# fabduck_01.net
KiCad netlist of a schematic drawn in EAGLE
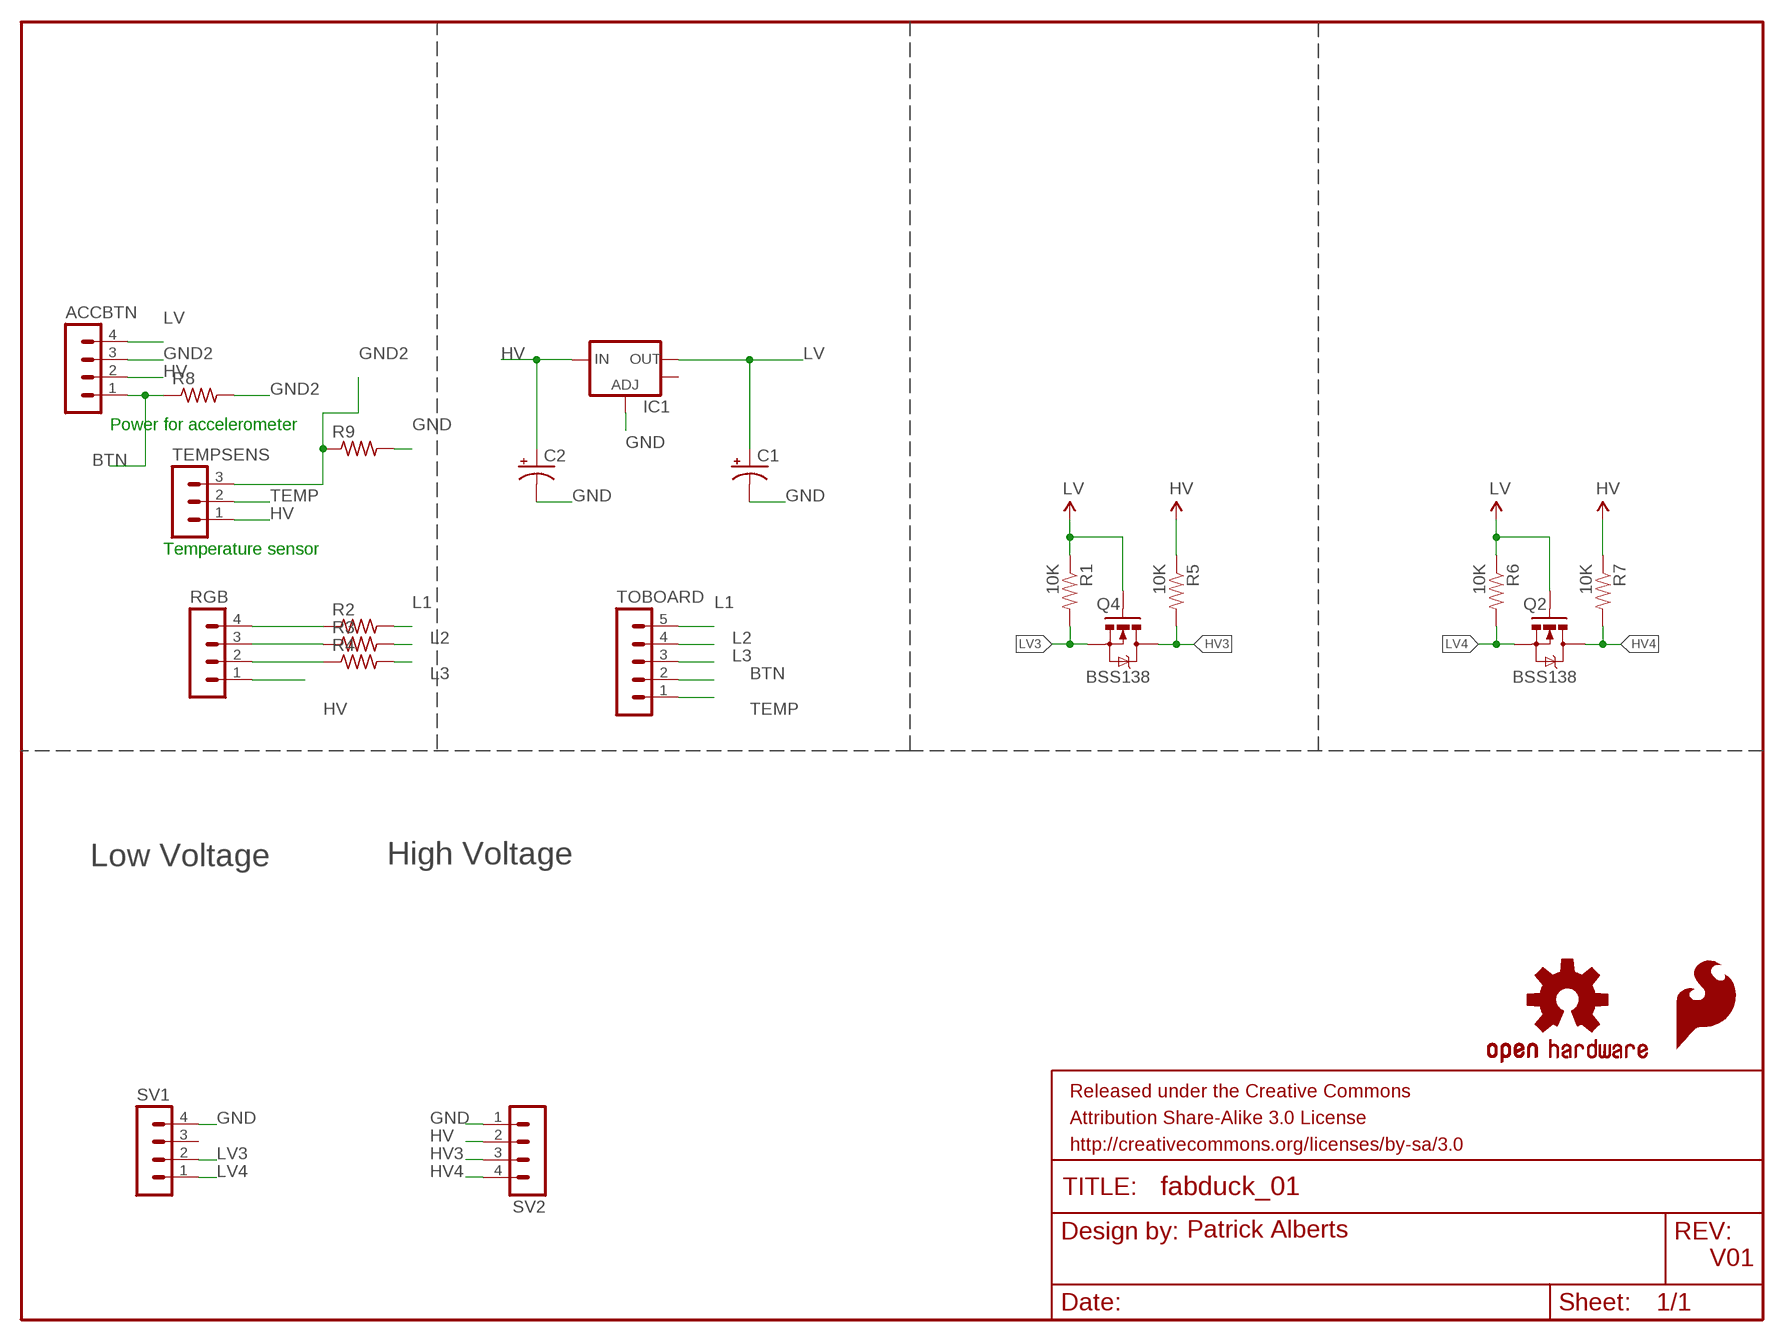
[diagram p0: schematic, sheet 1]

(export (version "E")
  (design (tool "Eeschema 10.0.6"))
  (components
    (comp (ref "ACCBTN")
      (value "MA04-1")
      (footprint "eagle-import:MA04-1")
      (libsource (lib "eagle-import") (part "MA04-1"))
    )
    (comp (ref "C1")
      (value "CAP_POLD")
      (footprint "eagle-import:PANASONIC_D")
      (libsource (lib "eagle-import") (part "CAP_POLD"))
    )
    (comp (ref "C2")
      (value "CAP_POLD")
      (footprint "eagle-import:PANASONIC_D")
      (libsource (lib "eagle-import") (part "CAP_POLD"))
    )
    (comp (ref "IC1")
      (value "V_REG_LM1117SOT223")
      (footprint "eagle-import:SOT223")
      (libsource (lib "eagle-import") (part "V_REG_LM1117SOT223"))
    )
    (comp (ref "LOGO1")
      (value "SFE_LOGO_FLAME.1_INCH")
      (footprint "eagle-import:SFE_LOGO_FLAME_.1")
      (libsource (lib "eagle-import") (part "SFE_LOGO_FLAME.1_INCH"))
    )
    (comp (ref "LOGO2")
      (value "OSHW-LOGOS")
      (footprint "eagle-import:OSHW-LOGO-S")
      (libsource (lib "eagle-import") (part "OSHW-LOGOS"))
    )
    (comp (ref "Q2")
      (value "BSS138")
      (footprint "eagle-import:SOT23-3")
      (libsource (lib "eagle-import") (part "MOSFET-NCHANNELSMD"))
    )
    (comp (ref "Q4")
      (value "BSS138")
      (footprint "eagle-import:SOT23-3")
      (libsource (lib "eagle-import") (part "MOSFET-NCHANNELSMD"))
    )
    (comp (ref "R1")
      (value "10K")
      (footprint "eagle-import:0603-RES")
      (libsource (lib "eagle-import") (part "RESISTOR0603-RES"))
    )
    (comp (ref "R2")
      (value "RESISTOR1206")
      (footprint "eagle-import:1206")
      (libsource (lib "eagle-import") (part "RESISTOR1206"))
    )
    (comp (ref "R3")
      (value "RESISTOR1206")
      (footprint "eagle-import:1206")
      (libsource (lib "eagle-import") (part "RESISTOR1206"))
    )
    (comp (ref "R4")
      (value "RESISTOR1206")
      (footprint "eagle-import:1206")
      (libsource (lib "eagle-import") (part "RESISTOR1206"))
    )
    (comp (ref "R5")
      (value "10K")
      (footprint "eagle-import:0603-RES")
      (libsource (lib "eagle-import") (part "RESISTOR0603-RES"))
    )
    (comp (ref "R6")
      (value "10K")
      (footprint "eagle-import:0603-RES")
      (libsource (lib "eagle-import") (part "RESISTOR0603-RES"))
    )
    (comp (ref "R7")
      (value "10K")
      (footprint "eagle-import:0603-RES")
      (libsource (lib "eagle-import") (part "RESISTOR0603-RES"))
    )
    (comp (ref "R8")
      (value "RESISTOR1206")
      (footprint "eagle-import:1206")
      (libsource (lib "eagle-import") (part "RESISTOR1206"))
    )
    (comp (ref "R9")
      (value "RESISTOR1206")
      (footprint "eagle-import:1206")
      (libsource (lib "eagle-import") (part "RESISTOR1206"))
    )
    (comp (ref "RGB")
      (value "MA04-1")
      (footprint "eagle-import:MA04-1")
      (libsource (lib "eagle-import") (part "MA04-1"))
    )
    (comp (ref "SV1")
      (value "MA04-1")
      (footprint "eagle-import:MA04-1")
      (libsource (lib "eagle-import") (part "MA04-1"))
    )
    (comp (ref "SV2")
      (value "MA04-1")
      (footprint "eagle-import:MA04-1")
      (libsource (lib "eagle-import") (part "MA04-1"))
    )
    (comp (ref "TEMPSENS")
      (value "MA03-1")
      (footprint "eagle-import:MA03-1")
      (libsource (lib "eagle-import") (part "MA03-1"))
    )
    (comp (ref "TOBOARD")
      (value "MA05-1")
      (footprint "eagle-import:MA05-1")
      (libsource (lib "eagle-import") (part "MA05-1"))
    )
  )
  (nets
    (net (code "1") (name "/BTN") (class "Default")
      (node (ref "ACCBTN") (pin "1") (pinfunction "1_1") (pintype "passive"))
      (node (ref "R8") (pin "1") (pinfunction "1_1") (pintype "passive"))
      (node (ref "TOBOARD") (pin "2") (pinfunction "2_2") (pintype "passive"))
    )
    (net (code "2") (name "/GND") (class "Default")
      (node (ref "C1") (pin "-") (pinfunction "-_-") (pintype "passive"))
      (node (ref "C2") (pin "-") (pinfunction "-_-") (pintype "passive"))
      (node (ref "IC1") (pin "1") (pinfunction "ADJ_1") (pintype "input"))
      (node (ref "R9") (pin "2") (pinfunction "2_2") (pintype "passive"))
      (node (ref "SV1") (pin "4") (pinfunction "4_4") (pintype "passive"))
      (node (ref "SV2") (pin "1") (pinfunction "1_1") (pintype "passive"))
    )
    (net (code "3") (name "/GND2") (class "Default")
      (node (ref "ACCBTN") (pin "3") (pinfunction "3_3") (pintype "passive"))
      (node (ref "R8") (pin "2") (pinfunction "2_2") (pintype "passive"))
      (node (ref "R9") (pin "1") (pinfunction "1_1") (pintype "passive"))
      (node (ref "TEMPSENS") (pin "3") (pinfunction "3_3") (pintype "passive"))
    )
    (net (code "4") (name "/L1") (class "Default")
      (node (ref "R2") (pin "2") (pinfunction "2_2") (pintype "passive"))
      (node (ref "TOBOARD") (pin "5") (pinfunction "5_5") (pintype "passive"))
    )
    (net (code "5") (name "/L2") (class "Default")
      (node (ref "R3") (pin "2") (pinfunction "2_2") (pintype "passive"))
      (node (ref "TOBOARD") (pin "4") (pinfunction "4_4") (pintype "passive"))
    )
    (net (code "6") (name "/L3") (class "Default")
      (node (ref "R4") (pin "2") (pinfunction "2_2") (pintype "passive"))
      (node (ref "TOBOARD") (pin "3") (pinfunction "3_3") (pintype "passive"))
    )
    (net (code "7") (name "/TEMP") (class "Default")
      (node (ref "TEMPSENS") (pin "2") (pinfunction "2_2") (pintype "passive"))
      (node (ref "TOBOARD") (pin "1") (pinfunction "1_1") (pintype "passive"))
    )
    (net (code "8") (name "HV") (class "Default")
      (node (ref "ACCBTN") (pin "2") (pinfunction "2_2") (pintype "passive"))
      (node (ref "C2") (pin "+") (pinfunction "+_+") (pintype "passive"))
      (node (ref "IC1") (pin "3") (pinfunction "IN_3") (pintype "input"))
      (node (ref "R5") (pin "1") (pinfunction "1_1") (pintype "passive"))
      (node (ref "R7") (pin "1") (pinfunction "1_1") (pintype "passive"))
      (node (ref "RGB") (pin "1") (pinfunction "1_1") (pintype "passive"))
      (node (ref "SV2") (pin "2") (pinfunction "2_2") (pintype "passive"))
      (node (ref "TEMPSENS") (pin "1") (pinfunction "1_1") (pintype "passive"))
    )
    (net (code "9") (name "HV3") (class "Default")
      (node (ref "Q4") (pin "3") (pinfunction "D_3") (pintype "passive"))
      (node (ref "R5") (pin "2") (pinfunction "2_2") (pintype "passive"))
      (node (ref "SV2") (pin "3") (pinfunction "3_3") (pintype "passive"))
    )
    (net (code "10") (name "HV4") (class "Default")
      (node (ref "Q2") (pin "3") (pinfunction "D_3") (pintype "passive"))
      (node (ref "R7") (pin "2") (pinfunction "2_2") (pintype "passive"))
      (node (ref "SV2") (pin "4") (pinfunction "4_4") (pintype "passive"))
    )
    (net (code "11") (name "LV") (class "Default")
      (node (ref "ACCBTN") (pin "4") (pinfunction "4_4") (pintype "passive"))
      (node (ref "C1") (pin "+") (pinfunction "+_+") (pintype "passive"))
      (node (ref "IC1") (pin "2") (pinfunction "OUT_2") (pintype "output"))
      (node (ref "Q2") (pin "1") (pinfunction "G_1") (pintype "passive"))
      (node (ref "Q4") (pin "1") (pinfunction "G_1") (pintype "passive"))
      (node (ref "R1") (pin "1") (pinfunction "1_1") (pintype "passive"))
      (node (ref "R6") (pin "1") (pinfunction "1_1") (pintype "passive"))
    )
    (net (code "12") (name "LV3") (class "Default")
      (node (ref "Q4") (pin "2") (pinfunction "S_2") (pintype "passive"))
      (node (ref "R1") (pin "2") (pinfunction "2_2") (pintype "passive"))
      (node (ref "SV1") (pin "2") (pinfunction "2_2") (pintype "passive"))
    )
    (net (code "13") (name "LV4") (class "Default")
      (node (ref "Q2") (pin "2") (pinfunction "S_2") (pintype "passive"))
      (node (ref "R6") (pin "2") (pinfunction "2_2") (pintype "passive"))
      (node (ref "SV1") (pin "1") (pinfunction "1_1") (pintype "passive"))
    )
    (net (code "14") (name "Net-(R2-Pad1)") (class "Default")
      (node (ref "R2") (pin "1") (pinfunction "1_1") (pintype "passive"))
      (node (ref "RGB") (pin "4") (pinfunction "4_4") (pintype "passive"))
    )
    (net (code "15") (name "Net-(R3-Pad1)") (class "Default")
      (node (ref "R3") (pin "1") (pinfunction "1_1") (pintype "passive"))
      (node (ref "RGB") (pin "3") (pinfunction "3_3") (pintype "passive"))
    )
    (net (code "16") (name "Net-(R4-Pad1)") (class "Default")
      (node (ref "R4") (pin "1") (pinfunction "1_1") (pintype "passive"))
      (node (ref "RGB") (pin "2") (pinfunction "2_2") (pintype "passive"))
    )
    (net (code "17") (name "unconnected-(IC1-OUT-Pad4)") (class "Default")
      (node (ref "IC1") (pin "4") (pinfunction "OUT_4") (pintype "output"))
    )
    (net (code "18") (name "unconnected-(SV1-Pad3)") (class "Default")
      (node (ref "SV1") (pin "3") (pinfunction "3_3") (pintype "passive"))
    )
  )
)
